# 05_-_CPU_-_HDMI_LVDS.net
KiCad netlist of a schematic drawn in Altium Designer
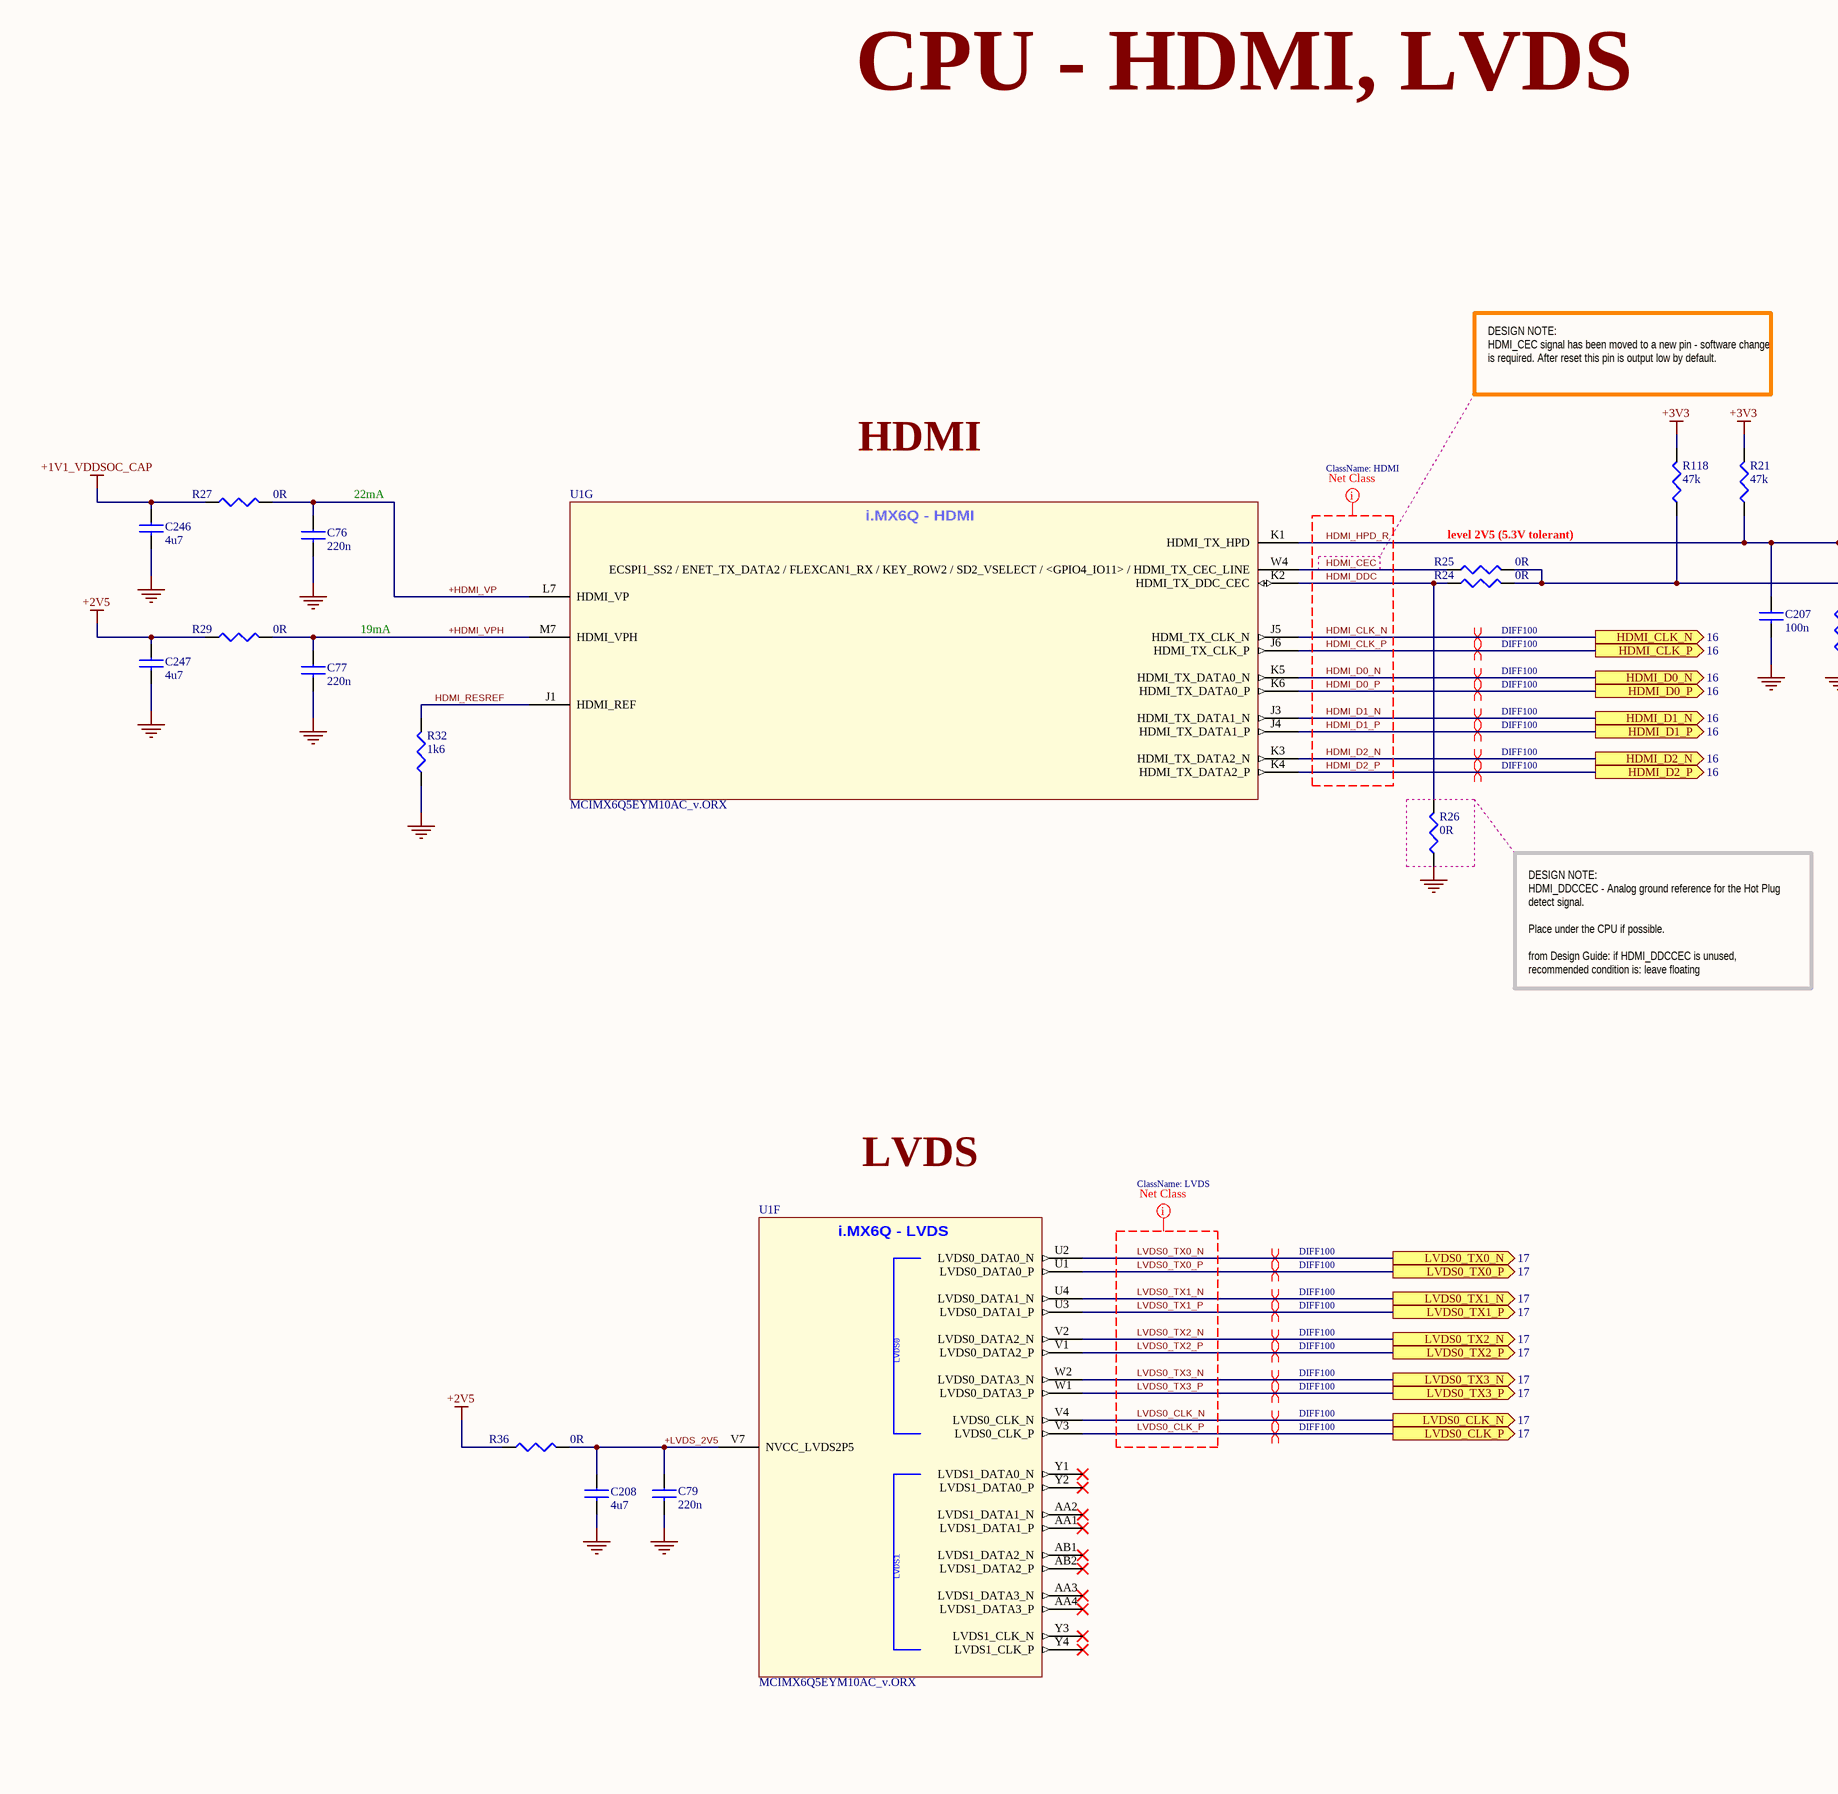
[diagram p0: [05] - CPU - HDMI, LVDS.SchDoc, left]
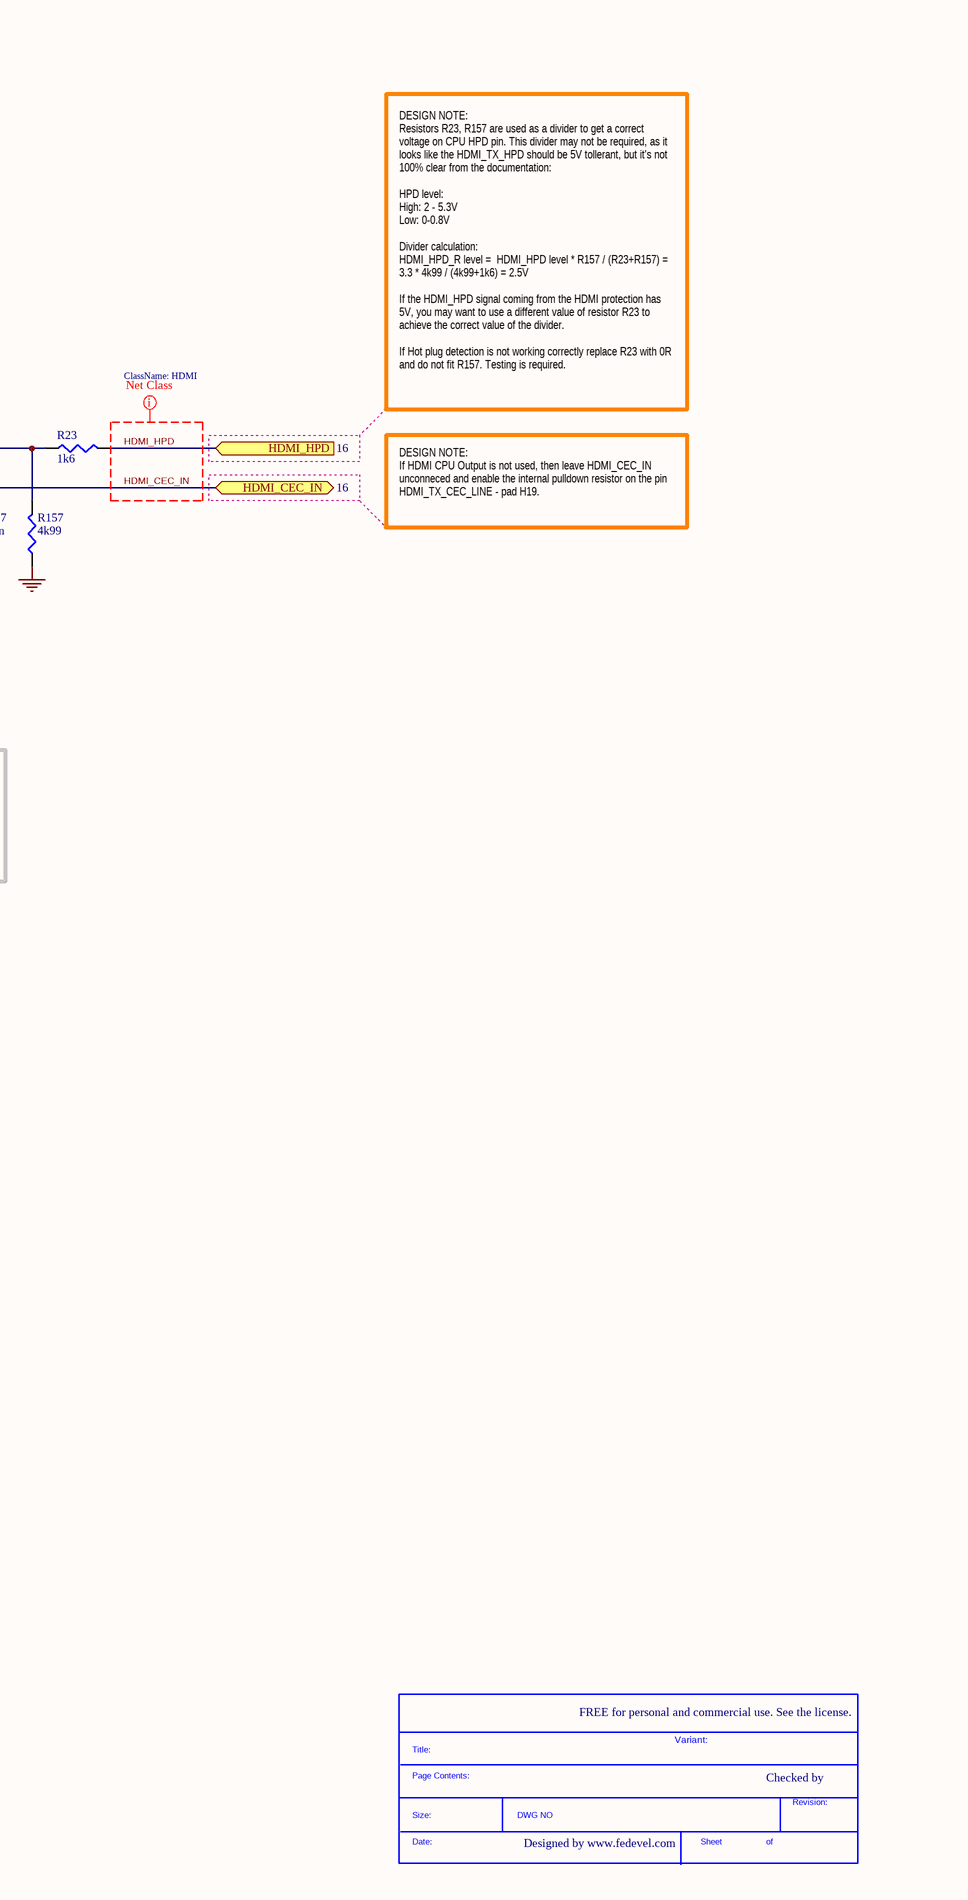
[diagram p1: [05] - CPU - HDMI, LVDS.SchDoc, right]

(export (version "E")
  (design (tool "Eeschema 10.0.6"))
  (components
    (comp (ref "C76")
      (value "220n")
      (footprint "C0201")
      (description "CAP CER 0.22UF 6.3V 20% X5R 0201")
      (fields
        (field (name "MANUFACTURER") "TDK Corporation")
        (field (name "MANUFACTURER PART NUMBER") "C0603X5R0J224M030BB")
        (field (name ".CHECKED PCB") "MM")
        (field (name ".CHECKED SCH") "MM")
        (field (name ".CREATOR") "MM")
      )
      (libsource (lib "Integrated_Library_FEDEVEL_0201") (part "C0603X5R0J224M030BB"))
    )
    (comp (ref "C77")
      (value "220n")
      (footprint "C0201")
      (description "CAP CER 0.22UF 6.3V 20% X5R 0201")
      (fields
        (field (name "MANUFACTURER") "TDK Corporation")
        (field (name "MANUFACTURER PART NUMBER") "C0603X5R0J224M030BB")
        (field (name ".CHECKED PCB") "MM")
        (field (name ".CHECKED SCH") "MM")
        (field (name ".CREATOR") "MM")
      )
      (libsource (lib "Integrated_Library_FEDEVEL_0201") (part "C0603X5R0J224M030BB"))
    )
    (comp (ref "C79")
      (value "220n")
      (footprint "C0201")
      (description "CAP CER 0.22UF 6.3V 20% X5R 0201")
      (fields
        (field (name "MANUFACTURER") "TDK Corporation")
        (field (name "MANUFACTURER PART NUMBER") "C0603X5R0J224M030BB")
        (field (name ".CHECKED PCB") "MM")
        (field (name ".CHECKED SCH") "MM")
        (field (name ".CREATOR") "MM")
      )
      (libsource (lib "Integrated_Library_FEDEVEL_0201") (part "C0603X5R0J224M030BB"))
    )
    (comp (ref "C207")
      (value "100n")
      (footprint "C0402")
      (description "CAP CER .10UF 50V X5R 10% 0402")
      (fields
        (field (name "MANUFACTURER") "TDK Corporation")
        (field (name "MANUFACTURER PART NUMBER") "C1005X5R1H104K")
      )
      (libsource (lib "Integrated_Library_FEDEVEL_APR_2015") (part "C1005X5R1H104K"))
    )
    (comp (ref "C208")
      (value "4u7")
      (footprint "C0402")
      (description "CAP CER 4.7UF 10V 20% X5R 0402")
      (fields
        (field (name "MANUFACTURER") "TDK Corporation")
        (field (name "MANUFACTURER PART NUMBER") "C1005X5R1A475M")
      )
      (libsource (lib "Integrated_Library_FEDEVEL_APR_2015") (part "C1005X5R1A475M"))
    )
    (comp (ref "C246")
      (value "4u7")
      (footprint "C0402")
      (description "CAP CER 4.7UF 10V 20% X5R 0402")
      (fields
        (field (name "MANUFACTURER") "TDK Corporation")
        (field (name "MANUFACTURER PART NUMBER") "C1005X5R1A475M")
      )
      (libsource (lib "Integrated_Library_FEDEVEL_APR_2015") (part "C1005X5R1A475M"))
    )
    (comp (ref "C247")
      (value "4u7")
      (footprint "C0402")
      (description "CAP CER 4.7UF 10V 20% X5R 0402")
      (fields
        (field (name "MANUFACTURER") "TDK Corporation")
        (field (name "MANUFACTURER PART NUMBER") "C1005X5R1A475M")
      )
      (libsource (lib "Integrated_Library_FEDEVEL_APR_2015") (part "C1005X5R1A475M"))
    )
    (comp (ref "R21")
      (value "47k")
      (footprint "R0402")
      (description "RES 47.0K OHM 1/16W 1% 0402 SMD")
      (fields
        (field (name "MANUFACTURER") "Yageo")
        (field (name "MANUFACTURER PART NUMBER") "RC0402FR-0747KL")
      )
      (libsource (lib "Integrated_Library_FEDEVEL_APR_2015") (part "RC0402FR-0747KL"))
    )
    (comp (ref "R23")
      (value "1k6")
      (footprint "R0402")
      (description "RES 1.6K OHM 1/10W 1% 0402 SMD")
      (fields
        (field (name "MANUFACTURER") "Panasonic Electronic Components")
        (field (name "MANUFACTURER PART NUMBER") "ERJ-2RKF1601X")
        (field (name ".CREATOR") "MM")
      )
      (libsource (lib "Integrated_Library_FEDEVEL_APR_2015") (part "ERJ-2RKF1601X"))
    )
    (comp (ref "R24")
      (value "0R")
      (footprint "R0402")
      (description "RES 0.0 OHM 1/16W 0402 SMD")
      (fields
        (field (name "MANUFACTURER") "Yageo")
        (field (name "MANUFACTURER PART NUMBER") "RC0402JR-070RL")
      )
      (libsource (lib "Integrated_Library_FEDEVEL_APR_2015") (part "RC0402JR-070RL"))
    )
    (comp (ref "R25")
      (value "0R")
      (footprint "R0402")
      (description "RES 0.0 OHM 1/16W 0402 SMD")
      (fields
        (field (name "MANUFACTURER") "Yageo")
        (field (name "MANUFACTURER PART NUMBER") "RC0402JR-070RL")
      )
      (libsource (lib "Integrated_Library_FEDEVEL_APR_2015") (part "RC0402JR-070RL"))
    )
    (comp (ref "R26")
      (value "0R")
      (footprint "R0402")
      (description "RES 0.0 OHM 1/16W 0402 SMD")
      (fields
        (field (name "MANUFACTURER") "Yageo")
        (field (name "MANUFACTURER PART NUMBER") "RC0402JR-070RL")
      )
      (libsource (lib "Integrated_Library_FEDEVEL_APR_2015") (part "RC0402JR-070RL"))
    )
    (comp (ref "R27")
      (value "0R")
      (footprint "R0402")
      (description "RES 0.0 OHM 1/16W 0402 SMD")
      (fields
        (field (name "MANUFACTURER") "Yageo")
        (field (name "MANUFACTURER PART NUMBER") "RC0402JR-070RL")
      )
      (libsource (lib "Integrated_Library_FEDEVEL_APR_2015") (part "RC0402JR-070RL"))
    )
    (comp (ref "R29")
      (value "0R")
      (footprint "R0402")
      (description "RES 0.0 OHM 1/16W 0402 SMD")
      (fields
        (field (name "MANUFACTURER") "Yageo")
        (field (name "MANUFACTURER PART NUMBER") "RC0402JR-070RL")
      )
      (libsource (lib "Integrated_Library_FEDEVEL_APR_2015") (part "RC0402JR-070RL"))
    )
    (comp (ref "R32")
      (value "1k6")
      (footprint "R0201")
      (description "RES 1.60K OHM 1/20W 1% 0201 SMD")
      (fields
        (field (name "MANUFACTURER") "Vishay Dale")
        (field (name "MANUFACTURER PART NUMBER") "CRCW02011K60FKED")
        (field (name ".CREATOR") "MM")
        (field (name ".CHECKED PCB") "MM")
        (field (name ".CHECKED SCH") "MM")
      )
      (libsource (lib "Integrated_Library_FEDEVEL_0201") (part "CRCW02011K60FKED"))
    )
    (comp (ref "R36")
      (value "0R")
      (footprint "R0402")
      (description "RES 0.0 OHM 1/16W 0402 SMD")
      (fields
        (field (name "MANUFACTURER") "Yageo")
        (field (name "MANUFACTURER PART NUMBER") "RC0402JR-070RL")
      )
      (libsource (lib "Integrated_Library_FEDEVEL_APR_2015") (part "RC0402JR-070RL"))
    )
    (comp (ref "R118")
      (value "47k")
      (footprint "R0402")
      (description "RES 47.0K OHM 1/16W 1% 0402 SMD")
      (fields
        (field (name "MANUFACTURER") "Yageo")
        (field (name "MANUFACTURER PART NUMBER") "RC0402FR-0747KL")
      )
      (libsource (lib "Integrated_Library_FEDEVEL_APR_2015") (part "RC0402FR-0747KL"))
    )
    (comp (ref "R157")
      (value "4k99")
      (footprint "R0402")
      (description "RES TF 4.99K OHM 1% 1/16W 0402")
      (fields
        (field (name "MANUFACTURER") "Stackpole Electronics Inc")
        (field (name "MANUFACTURER PART NUMBER") "RMCF0402FT4K99")
      )
      (libsource (lib "Integrated_Library_FEDEVEL_APR_2015") (part "RMCF0402FT4K99"))
    )
    (comp (ref "U1")
      (value "MCIMX6Q5EYM10AC_v.ORX")
      (footprint "PBGA624")
      (description "IC MCU 32BIT ARM QUAD 624FCBGA")
      (fields
        (field (name "MANUFACTURER") "Freescale Semiconductor")
        (field (name "MANUFACTURER PART NUMBER") "MCIMX6Q5EYM10AC")
        (field (name ".CREATOR") "MM")
        (field (name ".CHECKED PCB") "MM, checked by RF")
      )
      (libsource (lib "Integrated_Library_FEDEVEL_APR_2015") (part "MCIMX6Q5EYM10AC_v.ORX"))
    )
  )
  (nets
    (net (code "1") (name "+1V1_VDDSOC_CAP") (class "Default")
      (node (ref "C246") (pin "1") (pinfunction "1_1") (pintype "passive"))
      (node (ref "R27") (pin "1") (pinfunction "1_1") (pintype "passive"))
    )
    (net (code "2") (name "+2V5") (class "Default")
      (node (ref "C247") (pin "1") (pinfunction "1_1") (pintype "passive"))
      (node (ref "R29") (pin "1") (pinfunction "1_1") (pintype "passive"))
      (node (ref "R36") (pin "1") (pinfunction "1_1") (pintype "passive"))
    )
    (net (code "3") (name "+3V3") (class "Default")
      (node (ref "R118") (pin "2") (pinfunction "2_2") (pintype "passive"))
      (node (ref "R21") (pin "2") (pinfunction "2_2") (pintype "passive"))
    )
    (net (code "4") (name "/+HDMI_VP") (class "Default")
      (node (ref "C76") (pin "1") (pinfunction "1_1") (pintype "passive"))
      (node (ref "R27") (pin "2") (pinfunction "2_2") (pintype "passive"))
      (node (ref "U1") (pin "L7") (pinfunction "HDMI_VP_L7") (pintype "power_in"))
    )
    (net (code "5") (name "/+HDMI_VPH") (class "Default")
      (node (ref "C77") (pin "1") (pinfunction "1_1") (pintype "passive"))
      (node (ref "R29") (pin "2") (pinfunction "2_2") (pintype "passive"))
      (node (ref "U1") (pin "M7") (pinfunction "HDMI_VPH_M7") (pintype "power_in"))
    )
    (net (code "6") (name "/+LVDS_2V5") (class "Default")
      (node (ref "C208") (pin "1") (pinfunction "1_1") (pintype "passive"))
      (node (ref "C79") (pin "1") (pinfunction "1_1") (pintype "passive"))
      (node (ref "R36") (pin "2") (pinfunction "2_2") (pintype "passive"))
      (node (ref "U1") (pin "V7") (pinfunction "NVCC_LVDS2P5_V7") (pintype "power_in"))
    )
    (net (code "7") (name "/HDMI_CEC") (class "Default")
      (node (ref "R25") (pin "1") (pinfunction "1_1") (pintype "passive"))
      (node (ref "U1") (pin "W4") (pinfunction "ECSPI1_SS2_/_ENET_TX_DATA2_/_FLEXCAN1_RX_/_KEY_ROW2_/_SD2_VSELECT_/_<GPIO4_IO11>_/_HDMI_TX_CEC_LINE_W4") (pintype "passive"))
    )
    (net (code "8") (name "/HDMI_CEC_IN") (class "Default")
      (node (ref "R118") (pin "1") (pinfunction "1_1") (pintype "passive"))
      (node (ref "R24") (pin "2") (pinfunction "2_2") (pintype "passive"))
      (node (ref "R25") (pin "2") (pinfunction "2_2") (pintype "passive"))
    )
    (net (code "9") (name "/HDMI_CLK_N") (class "Default")
      (node (ref "U1") (pin "J5") (pinfunction "HDMI_TX_CLK_N_J5") (pintype "output"))
    )
    (net (code "10") (name "/HDMI_CLK_P") (class "Default")
      (node (ref "U1") (pin "J6") (pinfunction "HDMI_TX_CLK_P_J6") (pintype "output"))
    )
    (net (code "11") (name "/HDMI_D0_N") (class "Default")
      (node (ref "U1") (pin "K5") (pinfunction "HDMI_TX_DATA0_N_K5") (pintype "output"))
    )
    (net (code "12") (name "/HDMI_D0_P") (class "Default")
      (node (ref "U1") (pin "K6") (pinfunction "HDMI_TX_DATA0_P_K6") (pintype "output"))
    )
    (net (code "13") (name "/HDMI_D1_N") (class "Default")
      (node (ref "U1") (pin "J3") (pinfunction "HDMI_TX_DATA1_N_J3") (pintype "output"))
    )
    (net (code "14") (name "/HDMI_D1_P") (class "Default")
      (node (ref "U1") (pin "J4") (pinfunction "HDMI_TX_DATA1_P_J4") (pintype "output"))
    )
    (net (code "15") (name "/HDMI_D2_N") (class "Default")
      (node (ref "U1") (pin "K3") (pinfunction "HDMI_TX_DATA2_N_K3") (pintype "output"))
    )
    (net (code "16") (name "/HDMI_D2_P") (class "Default")
      (node (ref "U1") (pin "K4") (pinfunction "HDMI_TX_DATA2_P_K4") (pintype "output"))
    )
    (net (code "17") (name "/HDMI_DDC") (class "Default")
      (node (ref "R24") (pin "1") (pinfunction "1_1") (pintype "passive"))
      (node (ref "R26") (pin "2") (pinfunction "2_2") (pintype "passive"))
      (node (ref "U1") (pin "K2") (pinfunction "HDMI_TX_DDC_CEC_K2") (pintype "bidirectional"))
    )
    (net (code "18") (name "/HDMI_HPD") (class "Default")
      (node (ref "R23") (pin "2") (pinfunction "2_2") (pintype "passive"))
    )
    (net (code "19") (name "/HDMI_HPD_R") (class "Default")
      (node (ref "C207") (pin "1") (pinfunction "1_1") (pintype "passive"))
      (node (ref "R157") (pin "2") (pinfunction "2_2") (pintype "passive"))
      (node (ref "R21") (pin "1") (pinfunction "1_1") (pintype "passive"))
      (node (ref "R23") (pin "1") (pinfunction "1_1") (pintype "passive"))
      (node (ref "U1") (pin "K1") (pinfunction "HDMI_TX_HPD_K1") (pintype "passive"))
    )
    (net (code "20") (name "/HDMI_RESREF") (class "Default")
      (node (ref "R32") (pin "2") (pinfunction "2_2") (pintype "passive"))
      (node (ref "U1") (pin "J1") (pinfunction "HDMI_REF_J1") (pintype "passive"))
    )
    (net (code "21") (name "/LVDS0_CLK_N") (class "Default")
      (node (ref "U1") (pin "V4") (pinfunction "LVDS0_CLK_N_V4") (pintype "output"))
    )
    (net (code "22") (name "/LVDS0_CLK_P") (class "Default")
      (node (ref "U1") (pin "V3") (pinfunction "LVDS0_CLK_P_V3") (pintype "output"))
    )
    (net (code "23") (name "/LVDS0_TX0_N") (class "Default")
      (node (ref "U1") (pin "U2") (pinfunction "LVDS0_DATA0_N_U2") (pintype "output"))
    )
    (net (code "24") (name "/LVDS0_TX0_P") (class "Default")
      (node (ref "U1") (pin "U1") (pinfunction "LVDS0_DATA0_P_U1") (pintype "output"))
    )
    (net (code "25") (name "/LVDS0_TX1_N") (class "Default")
      (node (ref "U1") (pin "U4") (pinfunction "LVDS0_DATA1_N_U4") (pintype "output"))
    )
    (net (code "26") (name "/LVDS0_TX1_P") (class "Default")
      (node (ref "U1") (pin "U3") (pinfunction "LVDS0_DATA1_P_U3") (pintype "output"))
    )
    (net (code "27") (name "/LVDS0_TX2_N") (class "Default")
      (node (ref "U1") (pin "V2") (pinfunction "LVDS0_DATA2_N_V2") (pintype "output"))
    )
    (net (code "28") (name "/LVDS0_TX2_P") (class "Default")
      (node (ref "U1") (pin "V1") (pinfunction "LVDS0_DATA2_P_V1") (pintype "output"))
    )
    (net (code "29") (name "/LVDS0_TX3_N") (class "Default")
      (node (ref "U1") (pin "W2") (pinfunction "LVDS0_DATA3_N_W2") (pintype "output"))
    )
    (net (code "30") (name "/LVDS0_TX3_P") (class "Default")
      (node (ref "U1") (pin "W1") (pinfunction "LVDS0_DATA3_P_W1") (pintype "output"))
    )
    (net (code "31") (name "GND") (class "Default")
      (node (ref "C207") (pin "2") (pinfunction "2_2") (pintype "passive"))
      (node (ref "C208") (pin "2") (pinfunction "2_2") (pintype "passive"))
      (node (ref "C246") (pin "2") (pinfunction "2_2") (pintype "passive"))
      (node (ref "C247") (pin "2") (pinfunction "2_2") (pintype "passive"))
      (node (ref "C76") (pin "2") (pinfunction "2_2") (pintype "passive"))
      (node (ref "C77") (pin "2") (pinfunction "2_2") (pintype "passive"))
      (node (ref "C79") (pin "2") (pinfunction "2_2") (pintype "passive"))
      (node (ref "R157") (pin "1") (pinfunction "1_1") (pintype "passive"))
      (node (ref "R26") (pin "1") (pinfunction "1_1") (pintype "passive"))
      (node (ref "R32") (pin "1") (pinfunction "1_1") (pintype "passive"))
    )
    (net (code "32") (name "unconnected-(U1F-LVDS1_CLK_N-PadY3)") (class "Default")
      (node (ref "U1") (pin "Y3") (pinfunction "LVDS1_CLK_N_Y3") (pintype "output+no_connect"))
    )
    (net (code "33") (name "unconnected-(U1F-LVDS1_CLK_P-PadY4)") (class "Default")
      (node (ref "U1") (pin "Y4") (pinfunction "LVDS1_CLK_P_Y4") (pintype "output+no_connect"))
    )
    (net (code "34") (name "unconnected-(U1F-LVDS1_DATA0_N-PadY1)") (class "Default")
      (node (ref "U1") (pin "Y1") (pinfunction "LVDS1_DATA0_N_Y1") (pintype "output+no_connect"))
    )
    (net (code "35") (name "unconnected-(U1F-LVDS1_DATA0_P-PadY2)") (class "Default")
      (node (ref "U1") (pin "Y2") (pinfunction "LVDS1_DATA0_P_Y2") (pintype "output+no_connect"))
    )
    (net (code "36") (name "unconnected-(U1F-LVDS1_DATA1_N-PadAA2)") (class "Default")
      (node (ref "U1") (pin "AA2") (pinfunction "LVDS1_DATA1_N_AA2") (pintype "output+no_connect"))
    )
    (net (code "37") (name "unconnected-(U1F-LVDS1_DATA1_P-PadAA1)") (class "Default")
      (node (ref "U1") (pin "AA1") (pinfunction "LVDS1_DATA1_P_AA1") (pintype "output+no_connect"))
    )
    (net (code "38") (name "unconnected-(U1F-LVDS1_DATA2_N-PadAB1)") (class "Default")
      (node (ref "U1") (pin "AB1") (pinfunction "LVDS1_DATA2_N_AB1") (pintype "output+no_connect"))
    )
    (net (code "39") (name "unconnected-(U1F-LVDS1_DATA2_P-PadAB2)") (class "Default")
      (node (ref "U1") (pin "AB2") (pinfunction "LVDS1_DATA2_P_AB2") (pintype "output+no_connect"))
    )
    (net (code "40") (name "unconnected-(U1F-LVDS1_DATA3_N-PadAA3)") (class "Default")
      (node (ref "U1") (pin "AA3") (pinfunction "LVDS1_DATA3_N_AA3") (pintype "output+no_connect"))
    )
    (net (code "41") (name "unconnected-(U1F-LVDS1_DATA3_P-PadAA4)") (class "Default")
      (node (ref "U1") (pin "AA4") (pinfunction "LVDS1_DATA3_P_AA4") (pintype "output+no_connect"))
    )
  )
)
